# pic_prog_breakout.net
KiCad netlist of a schematic drawn in EAGLE
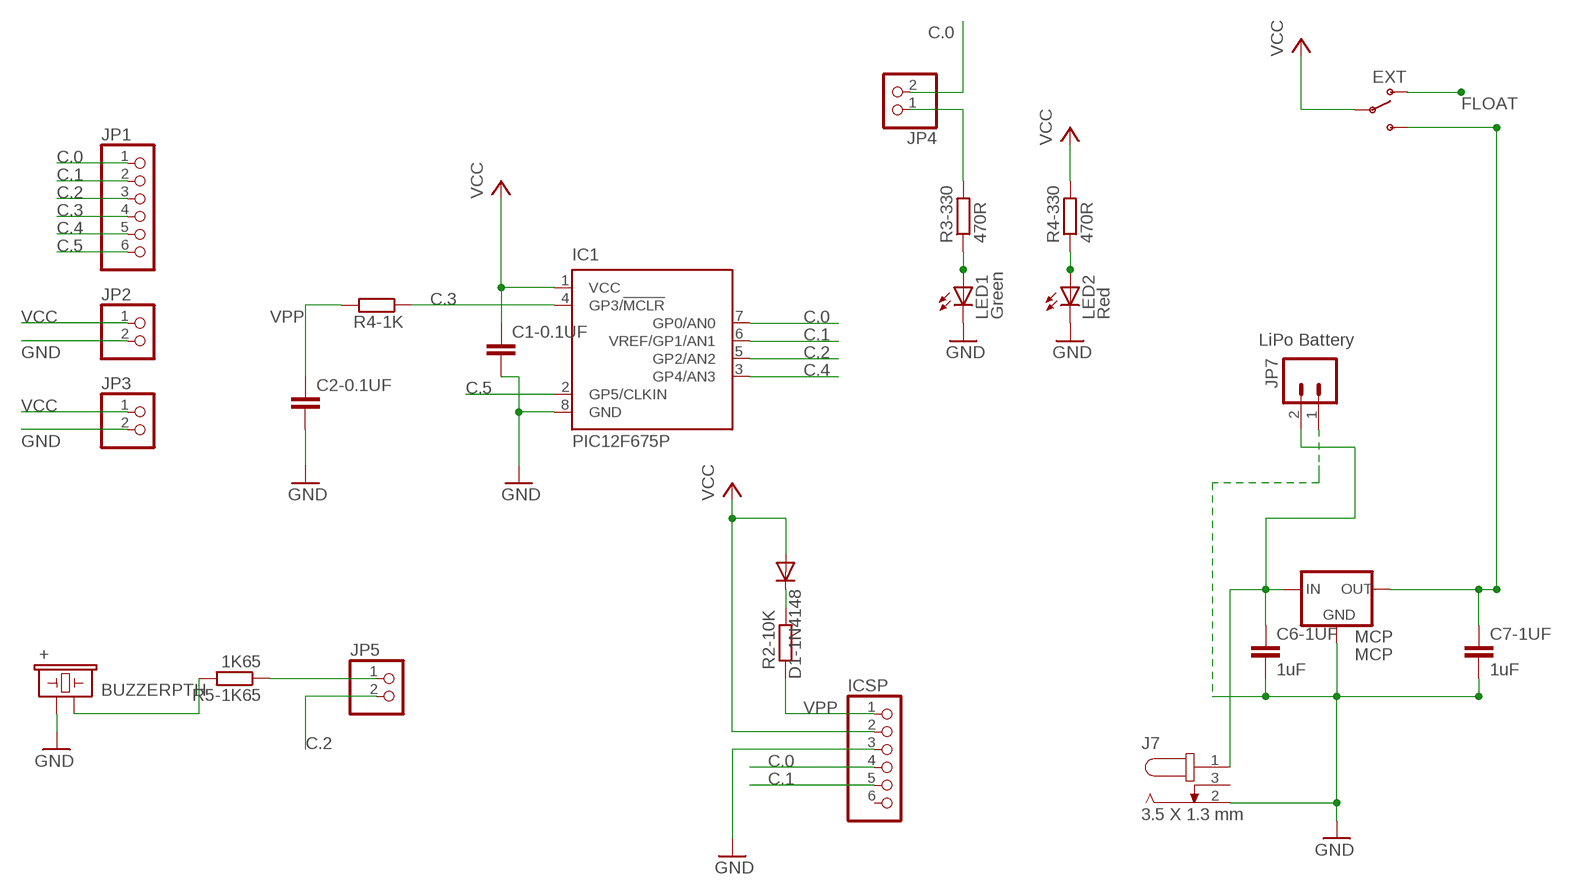
[diagram p0: schematic, sheet 1]

(export (version "E")
  (design (tool "Eeschema 10.0.6"))
  (components
    (comp (ref "+")
      (value "BUZZERPTH")
      (footprint "eagle-import:BUZZER-12MM")
      (libsource (lib "eagle-import") (part "BUZZERPTH"))
    )
    (comp (ref "C1-0.1UF")
      (value "C-EU025-025X050")
      (footprint "eagle-import:C025-025X050")
      (libsource (lib "eagle-import") (part "C-EU025-025X050"))
    )
    (comp (ref "C2-0.1UF")
      (value "C-EU025-025X050")
      (footprint "eagle-import:C025-025X050")
      (libsource (lib "eagle-import") (part "C-EU025-025X050"))
    )
    (comp (ref "C6-1UF")
      (value "1uF")
      (footprint "eagle-import:C050-025X075")
      (libsource (lib "eagle-import") (part "C-EU050-025X075"))
    )
    (comp (ref "C7-1UF")
      (value "1uF")
      (footprint "eagle-import:C050-025X075")
      (libsource (lib "eagle-import") (part "C-EU050-025X075"))
    )
    (comp (ref "D1-1N4148")
      (value "1N4148")
      (footprint "eagle-import:DO35-7")
      (libsource (lib "eagle-import") (part "1N4148DO35-7"))
    )
    (comp (ref "IC1")
      (value "PIC12F675P")
      (footprint "eagle-import:DIL8")
      (fields (field (name "MF") "MICROCHIP") (field (name "MPN") "PIC12F675-E/P"))
      (libsource (lib "eagle-import") (part "PIC12F675P"))
    )
    (comp (ref "ICSP")
      (value "PINHD-1X6")
      (footprint "eagle-import:1X06")
      (libsource (lib "eagle-import") (part "PINHD-1X6"))
    )
    (comp (ref "J7")
      (value "3.5 X 1.3 mm")
      (footprint "eagle-import:3.5X1.3MM_DC_JACK")
      (libsource (lib "eagle-import") (part "DC_JACK_3.5X1.3MM"))
    )
    (comp (ref "JP1")
      (value "PINHD-1X6")
      (footprint "eagle-import:1X06")
      (libsource (lib "eagle-import") (part "PINHD-1X6"))
    )
    (comp (ref "JP2")
      (value "PINHD-1X2")
      (footprint "eagle-import:1X02")
      (libsource (lib "eagle-import") (part "PINHD-1X2"))
    )
    (comp (ref "JP3")
      (value "PINHD-1X2")
      (footprint "eagle-import:1X02")
      (libsource (lib "eagle-import") (part "PINHD-1X2"))
    )
    (comp (ref "JP4")
      (value "PINHD-1X2")
      (footprint "eagle-import:1X02")
      (libsource (lib "eagle-import") (part "PINHD-1X2"))
    )
    (comp (ref "JP5")
      (value "PINHD-1X2")
      (footprint "eagle-import:1X02")
      (libsource (lib "eagle-import") (part "PINHD-1X2"))
    )
    (comp (ref "JP7")
      (value "LiPo Battery")
      (footprint "eagle-import:JST-2-PTH")
      (libsource (lib "eagle-import") (part "M02JST-PTH-2"))
    )
    (comp (ref "LED1")
      (value "Green")
      (footprint "eagle-import:LED3MM")
      (libsource (lib "eagle-import") (part "LED3MM"))
    )
    (comp (ref "LED2")
      (value "Red")
      (footprint "eagle-import:LED3MM")
      (libsource (lib "eagle-import") (part "LED3MM"))
    )
    (comp (ref "MCP")
      (value "MCP")
      (footprint "eagle-import:TO92-")
      (libsource (lib "eagle-import") (part "MCP1700TO-92"))
    )
    (comp (ref "ON")
      (value "EXT")
      (footprint "eagle-import:SWITCH-SPDT")
      (libsource (lib "eagle-import") (part "SWITCH-SPSTPTH"))
    )
    (comp (ref "R2-10K")
      (value "R-EU_0207/10")
      (footprint "eagle-import:0207_10")
      (libsource (lib "eagle-import") (part "R-EU_0207/10"))
    )
    (comp (ref "R3-330")
      (value "470R")
      (footprint "eagle-import:0207_10")
      (libsource (lib "eagle-import") (part "R-EU_0207/10"))
    )
    (comp (ref "R4-1K")
      (value "R-EU_0207/10")
      (footprint "eagle-import:0207_10")
      (libsource (lib "eagle-import") (part "R-EU_0207/10"))
    )
    (comp (ref "R4-330")
      (value "470R")
      (footprint "eagle-import:0207_10")
      (libsource (lib "eagle-import") (part "R-EU_0207/10"))
    )
    (comp (ref "R5-1K65")
      (value "1K65")
      (footprint "eagle-import:0207_10")
      (libsource (lib "eagle-import") (part "R-EU_0207/10"))
    )
  )
  (nets
    (net (code "1") (name "/C.0") (class "Default")
      (node (ref "IC1") (pin "7") (pinfunction "GP0/AN0_7") (pintype "bidirectional"))
      (node (ref "ICSP") (pin "4") (pinfunction "4_4") (pintype "passive"))
      (node (ref "JP1") (pin "1") (pinfunction "1_1") (pintype "passive"))
      (node (ref "JP4") (pin "2") (pinfunction "2_2") (pintype "passive"))
    )
    (net (code "2") (name "/C.1") (class "Default")
      (node (ref "IC1") (pin "6") (pinfunction "VREF/GP1/AN1_6") (pintype "bidirectional"))
      (node (ref "ICSP") (pin "5") (pinfunction "5_5") (pintype "passive"))
      (node (ref "JP1") (pin "2") (pinfunction "2_2") (pintype "passive"))
    )
    (net (code "3") (name "/C.2") (class "Default")
      (node (ref "IC1") (pin "5") (pinfunction "GP2/AN2_5") (pintype "bidirectional"))
      (node (ref "JP1") (pin "3") (pinfunction "3_3") (pintype "passive"))
      (node (ref "JP5") (pin "2") (pinfunction "2_2") (pintype "passive"))
    )
    (net (code "4") (name "/C.3") (class "Default")
      (node (ref "IC1") (pin "4") (pinfunction "GP3/~{MCLR}_4") (pintype "input"))
      (node (ref "JP1") (pin "4") (pinfunction "4_4") (pintype "passive"))
      (node (ref "R4-1K") (pin "1") (pinfunction "1_1") (pintype "passive"))
    )
    (net (code "5") (name "/C.4") (class "Default")
      (node (ref "IC1") (pin "3") (pinfunction "GP4/AN3_3") (pintype "bidirectional"))
      (node (ref "JP1") (pin "5") (pinfunction "5_5") (pintype "passive"))
    )
    (net (code "6") (name "/C.5") (class "Default")
      (node (ref "IC1") (pin "2") (pinfunction "GP5/CLKIN_2") (pintype "bidirectional"))
      (node (ref "JP1") (pin "6") (pinfunction "6_6") (pintype "passive"))
    )
    (net (code "7") (name "/FLOAT") (class "Default")
      (node (ref "ON") (pin "1") (pinfunction "O_1") (pintype "passive"))
    )
    (net (code "8") (name "/VPP") (class "Default")
      (node (ref "C2-0.1UF") (pin "1") (pinfunction "1_1") (pintype "passive"))
      (node (ref "ICSP") (pin "1") (pinfunction "1_1") (pintype "passive"))
      (node (ref "R2-10K") (pin "1") (pinfunction "1_1") (pintype "passive"))
      (node (ref "R4-1K") (pin "2") (pinfunction "2_2") (pintype "passive"))
    )
    (net (code "9") (name "GND") (class "Default")
      (node (ref "+") (pin "+") (pinfunction "1_+") (pintype "passive"))
      (node (ref "C1-0.1UF") (pin "2") (pinfunction "2_2") (pintype "passive"))
      (node (ref "C2-0.1UF") (pin "2") (pinfunction "2_2") (pintype "passive"))
      (node (ref "C6-1UF") (pin "2") (pinfunction "2_2") (pintype "passive"))
      (node (ref "C7-1UF") (pin "2") (pinfunction "2_2") (pintype "passive"))
      (node (ref "IC1") (pin "8") (pinfunction "GND_8") (pintype "power_in"))
      (node (ref "ICSP") (pin "3") (pinfunction "3_3") (pintype "passive"))
      (node (ref "J7") (pin "2") (pinfunction "2_2") (pintype "passive"))
      (node (ref "JP2") (pin "2") (pinfunction "2_2") (pintype "passive"))
      (node (ref "JP3") (pin "2") (pinfunction "2_2") (pintype "passive"))
      (node (ref "JP7") (pin "1") (pinfunction "1_1") (pintype "passive"))
      (node (ref "LED1") (pin "K") (pinfunction "C_K") (pintype "passive"))
      (node (ref "LED2") (pin "K") (pinfunction "C_K") (pintype "passive"))
      (node (ref "MCP") (pin "3") (pinfunction "GND_3") (pintype "input"))
    )
    (net (code "10") (name "Net-(+-2)") (class "Default")
      (node (ref "+") (pin "-") (pinfunction "2_-") (pintype "passive"))
      (node (ref "R5-1K65") (pin "2") (pinfunction "2_2") (pintype "passive"))
    )
    (net (code "11") (name "Net-(D1-1N4148-PadC)") (class "Default")
      (node (ref "D1-1N4148") (pin "C") (pinfunction "C_C") (pintype "passive"))
      (node (ref "R2-10K") (pin "2") (pinfunction "2_2") (pintype "passive"))
    )
    (net (code "12") (name "Net-(JP4-Pad1)") (class "Default")
      (node (ref "JP4") (pin "1") (pinfunction "1_1") (pintype "passive"))
      (node (ref "R3-330") (pin "2") (pinfunction "2_2") (pintype "passive"))
    )
    (net (code "13") (name "Net-(JP5-Pad1)") (class "Default")
      (node (ref "JP5") (pin "1") (pinfunction "1_1") (pintype "passive"))
      (node (ref "R5-1K65") (pin "1") (pinfunction "1_1") (pintype "passive"))
    )
    (net (code "14") (name "Net-(LED1-PadA)") (class "Default")
      (node (ref "LED1") (pin "A") (pinfunction "A_A") (pintype "passive"))
      (node (ref "R3-330") (pin "1") (pinfunction "1_1") (pintype "passive"))
    )
    (net (code "15") (name "Net-(LED2-PadA)") (class "Default")
      (node (ref "LED2") (pin "A") (pinfunction "A_A") (pintype "passive"))
      (node (ref "R4-330") (pin "1") (pinfunction "1_1") (pintype "passive"))
    )
    (net (code "16") (name "Net-(MCP-IN)") (class "Default")
      (node (ref "C6-1UF") (pin "1") (pinfunction "1_1") (pintype "passive"))
      (node (ref "J7") (pin "1") (pinfunction "1_1") (pintype "passive"))
      (node (ref "JP7") (pin "2") (pinfunction "2_2") (pintype "passive"))
      (node (ref "MCP") (pin "2") (pinfunction "IN_2") (pintype "input"))
    )
    (net (code "17") (name "Net-(MCP-OUT)") (class "Default")
      (node (ref "C7-1UF") (pin "1") (pinfunction "1_1") (pintype "passive"))
      (node (ref "MCP") (pin "1") (pinfunction "OUT_1") (pintype "passive"))
      (node (ref "ON") (pin "3") (pinfunction "S_3") (pintype "passive"))
    )
    (net (code "18") (name "VCC") (class "Default")
      (node (ref "C1-0.1UF") (pin "1") (pinfunction "1_1") (pintype "passive"))
      (node (ref "D1-1N4148") (pin "A") (pinfunction "A_A") (pintype "passive"))
      (node (ref "IC1") (pin "1") (pinfunction "VCC_1") (pintype "power_in"))
      (node (ref "ICSP") (pin "2") (pinfunction "2_2") (pintype "passive"))
      (node (ref "JP2") (pin "1") (pinfunction "1_1") (pintype "passive"))
      (node (ref "JP3") (pin "1") (pinfunction "1_1") (pintype "passive"))
      (node (ref "ON") (pin "2") (pinfunction "P_2") (pintype "passive"))
      (node (ref "R4-330") (pin "2") (pinfunction "2_2") (pintype "passive"))
    )
    (net (code "19") (name "unconnected-(ICSP-Pad6)") (class "Default")
      (node (ref "ICSP") (pin "6") (pinfunction "6_6") (pintype "passive"))
    )
    (net (code "20") (name "unconnected-(J7-Pad3)") (class "Default")
      (node (ref "J7") (pin "3") (pinfunction "3_3") (pintype "passive"))
    )
  )
)
